# DIFF_DRV.net
KiCad netlist of a schematic drawn in Altium Designer
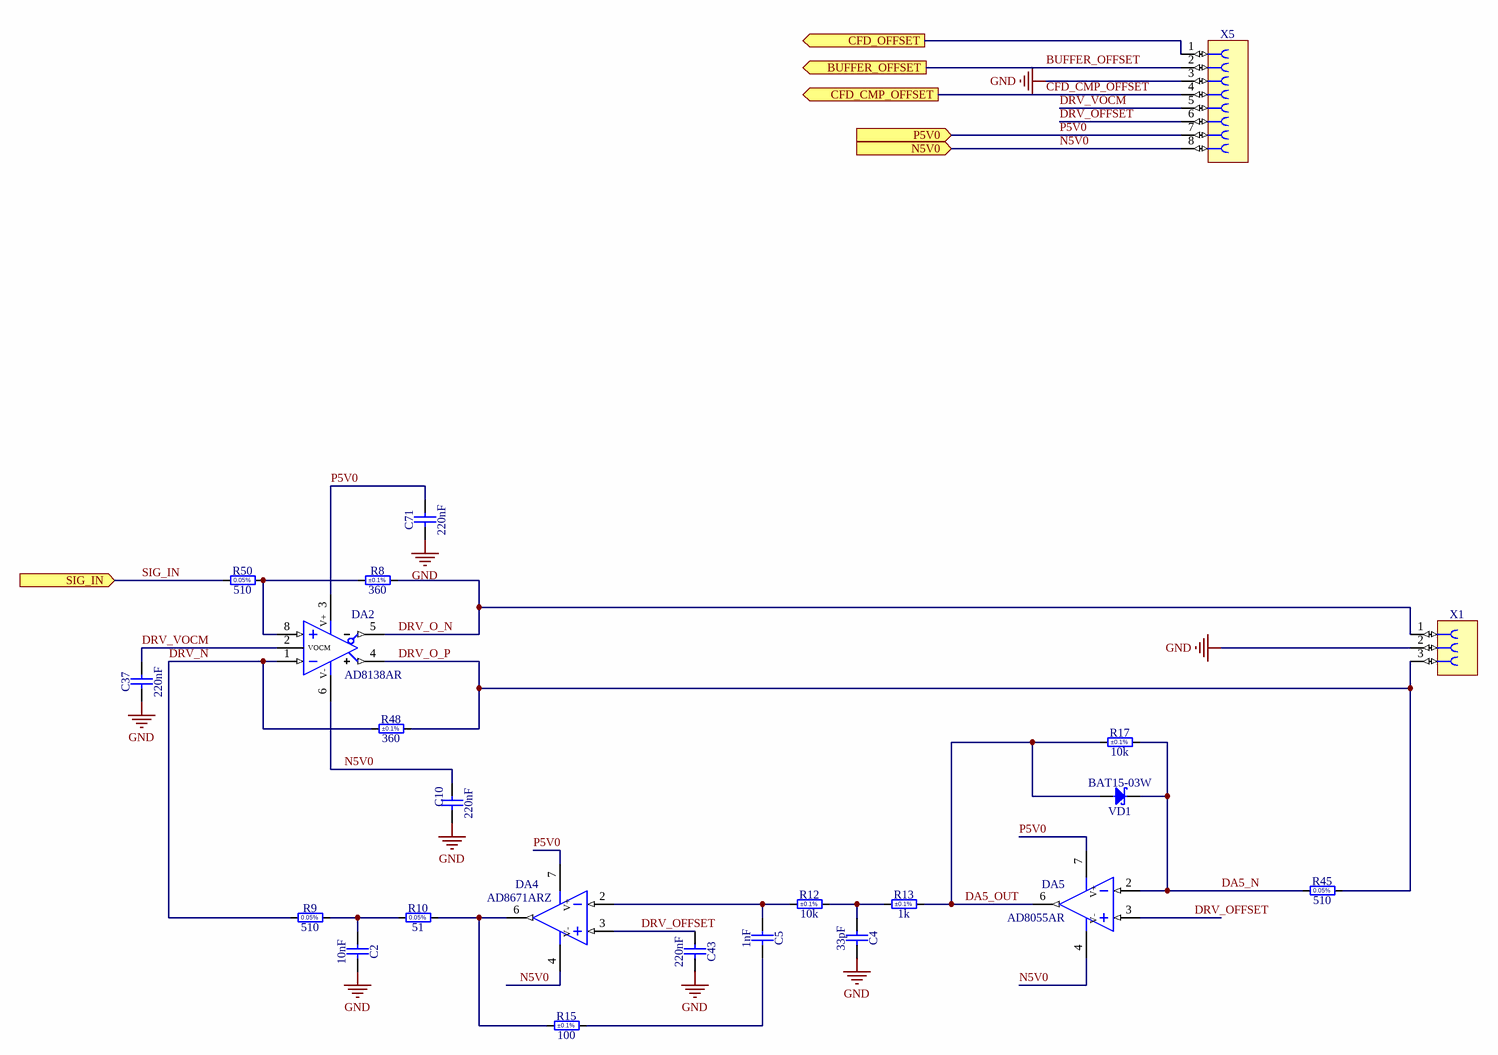
[diagram p0: DIFF_DRV.SchDoc]

(export (version "E")
  (design (tool "Eeschema 10.0.6"))
  (components
    (comp (ref "C2")
      (value "10nF")
      (footprint "CAPC2012X135N")
      (description "Non-polarised capacitor")
      (fields
        (field (name "PART NUMBER") "CC0805_10NF_50V_2%_C0G")
        (field (name "VOLTAGE") "50V")
        (field (name "AUTHOR") "CERN DEM HF")
      )
      (libsource (lib "Capacitors") (part "Capacitor - non polarized"))
    )
    (comp (ref "C4")
      (value "33pF")
      (footprint "CAPC2013X115N")
      (description "Non-polarised capacitor")
      (fields
        (field (name "PART NUMBER") "CC0805_33PF_200V_1%_NP0")
        (field (name "VOLTAGE") "200V")
        (field (name "AUTHOR") "CERN DEM HF")
      )
      (libsource (lib "Capacitors") (part "Capacitor - non polarized"))
    )
    (comp (ref "C5")
      (value "1nF")
      (footprint "CAPC2013X100N")
      (description "Non-polarised capacitor")
      (fields
        (field (name "PART NUMBER") "CC0805_1NF_25V_1%_C0G")
        (field (name "VOLTAGE") "25V")
        (field (name "AUTHOR") "CERN DEM JLC")
      )
      (libsource (lib "Capacitors") (part "Capacitor - non polarized"))
    )
    (comp (ref "C10")
      (value "220nF")
      (footprint "CAPC2012X135N")
      (description "Non-polarised capacitor")
      (fields
        (field (name "PART NUMBER") "CC0805_220NF_50V_10%_X7R")
        (field (name "VOLTAGE") "50V")
        (field (name "AUTHOR") "CERN DEM JLC")
      )
      (libsource (lib "Capacitors") (part "Capacitor - non polarized"))
    )
    (comp (ref "C37")
      (value "220nF")
      (footprint "CAPC2012X135N")
      (description "Non-polarised capacitor")
      (fields
        (field (name "PART NUMBER") "CC0805_220NF_50V_10%_X7R")
        (field (name "VOLTAGE") "50V")
        (field (name "AUTHOR") "CERN DEM JLC")
      )
      (libsource (lib "Capacitors") (part "Capacitor - non polarized"))
    )
    (comp (ref "C43")
      (value "220nF")
      (footprint "CAPC2012X135N")
      (description "Non-polarised capacitor")
      (fields
        (field (name "PART NUMBER") "CC0805_220NF_50V_10%_X7R")
        (field (name "VOLTAGE") "50V")
        (field (name "AUTHOR") "CERN DEM JLC")
      )
      (libsource (lib "Capacitors") (part "Capacitor - non polarized"))
    )
    (comp (ref "C71")
      (value "220nF")
      (footprint "CAPC2012X135N")
      (description "Non-polarised capacitor")
      (fields
        (field (name "PART NUMBER") "CC0805_220NF_50V_10%_X7R")
        (field (name "VOLTAGE") "50V")
        (field (name "AUTHOR") "CERN DEM JLC")
      )
      (libsource (lib "Capacitors") (part "Capacitor - non polarized"))
    )
    (comp (ref "DA2")
      (value "AD8138AR")
      (footprint "SOIC127P600X175-8N")
      (description "Differential Amplifier")
      (fields (field (name "MANUFACTURER") "ANALOG DEVICES") (field (name "AUTHOR") "CERN DEM JLC"))
      (libsource (lib "ICs And Semiconductors") (part "Differential Amplifier Type1"))
    )
    (comp (ref "DA4")
      (value "AD8671ARZ")
      (footprint "SOIC127P600X175-8N")
      (description "Operational Amplifier")
      (fields
        (field (name "MANUFACTURER") "ANALOG DEVICES")
        (field (name "MANUFACTURER PART NUMBER") "AD8671AR")
        (field (name "AUTHOR") "CERN DEM JLC")
      )
      (libsource (lib "ICs And Semiconductors") (part "Operational Amplifier Type1"))
    )
    (comp (ref "DA5")
      (value "AD8055AR")
      (footprint "SOIC127P600X175-8N")
      (description "Operational Amplifier")
      (fields (field (name "MANUFACTURER") "ANALOG DEVICES") (field (name "AUTHOR") "CERN DEM HF"))
      (libsource (lib "ICs And Semiconductors") (part "Operational Amplifier Type1"))
    )
    (comp (ref "R8")
      (value "360")
      (footprint "RESC2012X60N")
      (description "Resistor - 0.1%")
      (fields
        (field (name "TOLERANCE") "±0.1%")
        (field (name "PART NUMBER") "R0805_360R_0.1%_0.125W_10PPM")
        (field (name "POWER") "0.125W")
        (field (name "AUTHOR") "CERN DEM HF")
      )
      (libsource (lib "Resistors") (part "Resistor - 0.1%"))
    )
    (comp (ref "R9")
      (value "510")
      (footprint "RESC1608X55N")
      (description "Resistor - 0.05%")
      (fields
        (field (name "PART NUMBER") "R0603_510R_0.1%_0.1W_10PPM")
        (field (name "POWER") "0.1W")
        (field (name "AUTHOR") "CERN DEM HF")
      )
      (libsource (lib "Resistors") (part "Resistor - 0.05%"))
    )
    (comp (ref "R10")
      (value "51")
      (footprint "RESC2012X60N")
      (description "Resistor - 0.05%")
      (fields
        (field (name "PART NUMBER") "R0805_51R_0.05%_0.125W_10PPM")
        (field (name "POWER") "0.1W")
        (field (name "AUTHOR") "CERN DEM HF")
      )
      (libsource (lib "Resistors") (part "Resistor - 0.05%"))
    )
    (comp (ref "R12")
      (value "10k")
      (footprint "RESC2012X60N")
      (description "Resistor - 0.1%")
      (fields
        (field (name "TOLERANCE") "±0.1%")
        (field (name "PART NUMBER") "R0805_10K_0.1%_0.1W_10PPM")
        (field (name "POWER") "0.1W")
        (field (name "AUTHOR") "CERN DEM JLC")
      )
      (libsource (lib "Resistors") (part "Resistor - 0.1%"))
    )
    (comp (ref "R13")
      (value "1k")
      (footprint "RESC2012X60N")
      (description "Resistor - 0.1%")
      (fields
        (field (name "TOLERANCE") "±0.1%")
        (field (name "PART NUMBER") "R0805_1K_0.1%_0.1W_10PPM")
        (field (name "POWER") "0.1W")
        (field (name "AUTHOR") "CERN DEM JLC")
      )
      (libsource (lib "Resistors") (part "Resistor - 0.1%"))
    )
    (comp (ref "R15")
      (value "100")
      (footprint "RESC2012X60N")
      (description "Resistor - 0.1%")
      (fields
        (field (name "TOLERANCE") "±0.1%")
        (field (name "PART NUMBER") "R0805_100R_0.1%_0.1W_10PPM")
        (field (name "POWER") "0.1W")
        (field (name "AUTHOR") "CERN DEM JLC")
      )
      (libsource (lib "Resistors") (part "Resistor - 0.1%"))
    )
    (comp (ref "R17")
      (value "10k")
      (footprint "RESC2012X60N")
      (description "Resistor - 0.1%")
      (fields
        (field (name "TOLERANCE") "±0.1%")
        (field (name "PART NUMBER") "R0805_10K_0.1%_0.1W_10PPM")
        (field (name "POWER") "0.1W")
        (field (name "AUTHOR") "CERN DEM JLC")
      )
      (libsource (lib "Resistors") (part "Resistor - 0.1%"))
    )
    (comp (ref "R45")
      (value "510")
      (footprint "RESC1608X55N")
      (description "Resistor - 0.05%")
      (fields
        (field (name "PART NUMBER") "R0603_510R_0.1%_0.1W_10PPM")
        (field (name "POWER") "0.1W")
        (field (name "AUTHOR") "CERN DEM HF")
      )
      (libsource (lib "Resistors") (part "Resistor - 0.05%"))
    )
    (comp (ref "R48")
      (value "360")
      (footprint "RESC2012X60N")
      (description "Resistor - 0.1%")
      (fields
        (field (name "TOLERANCE") "±0.1%")
        (field (name "PART NUMBER") "R0805_360R_0.1%_0.125W_10PPM")
        (field (name "POWER") "0.125W")
        (field (name "AUTHOR") "CERN DEM HF")
      )
      (libsource (lib "Resistors") (part "Resistor - 0.1%"))
    )
    (comp (ref "R50")
      (value "510")
      (footprint "RESC1608X55N")
      (description "Resistor - 0.05%")
      (fields
        (field (name "PART NUMBER") "R0603_510R_0.1%_0.1W_10PPM")
        (field (name "POWER") "0.1W")
        (field (name "AUTHOR") "CERN DEM HF")
      )
      (libsource (lib "Resistors") (part "Resistor - 0.05%"))
    )
    (comp (ref "VD1")
      (value "BAT15-03W")
      (footprint "SOD2512X110N")
      (description "Schottky Diode")
      (fields
        (field (name "VOLTAGE") "4V")
        (field (name "POWER") "100mA")
        (field (name "AUTHOR") "CERN DEM HF")
      )
      (libsource (lib "ICs And Semiconductors") (part "Diode Schottky"))
    )
    (comp (ref "X1")
      (value "Socket 3")
      (footprint "SAMTEC_CES-103-01-T-S")
      (description "Connector 3 Female")
      (fields
        (field (name "PART NUMBER") "SAMTEC_CES-103-01-L-S")
        (field (name "MANUFACTURER") "SAMTEC")
        (field (name "AUTHOR") "CERN DEM HF")
      )
      (libsource (lib "Connectors") (part "Connector 3 Female"))
    )
    (comp (ref "X5")
      (value "Socket 8")
      (footprint "SAMTEC_CES-108-01-T-S")
      (description "Connector 8 Female")
      (fields
        (field (name "PART NUMBER") "SAMTEC_CES-108-01-L-S")
        (field (name "MANUFACTURER") "SAMTEC")
        (field (name "AUTHOR") "CERN DEM HF")
      )
      (libsource (lib "Connectors") (part "Connector 8 Female"))
    )
  )
  (nets
    (net (code "1") (name "/BUFFER_OFFSET") (class "Default")
      (node (ref "X5") (pin "2") (pinfunction "2_2") (pintype "bidirectional"))
    )
    (net (code "2") (name "/CFD_CMP_OFFSET") (class "Default")
      (node (ref "X5") (pin "4") (pinfunction "4_4") (pintype "bidirectional"))
    )
    (net (code "3") (name "/CFD_OFFSET") (class "Default")
      (node (ref "X5") (pin "1") (pinfunction "1_1") (pintype "bidirectional"))
    )
    (net (code "4") (name "/DA5_N") (class "Default")
      (node (ref "DA5") (pin "2") (pinfunction "IN-_2") (pintype "input"))
      (node (ref "R17") (pin "1") (pinfunction "1_1") (pintype "passive"))
      (node (ref "R45") (pin "1") (pinfunction "1_1") (pintype "passive"))
      (node (ref "VD1") (pin "1") (pinfunction "C_1") (pintype "passive"))
    )
    (net (code "5") (name "/DA5_OUT") (class "Default")
      (node (ref "DA5") (pin "6") (pinfunction "OUT_6") (pintype "output"))
      (node (ref "R13") (pin "1") (pinfunction "1_1") (pintype "passive"))
      (node (ref "R17") (pin "2") (pinfunction "2_2") (pintype "passive"))
      (node (ref "VD1") (pin "2") (pinfunction "A_2") (pintype "passive"))
    )
    (net (code "6") (name "/DRV_N") (class "Default")
      (node (ref "DA2") (pin "1") (pinfunction "IN-_1") (pintype "input"))
      (node (ref "R48") (pin "1") (pinfunction "1_1") (pintype "passive"))
      (node (ref "R9") (pin "2") (pinfunction "2_2") (pintype "passive"))
    )
    (net (code "7") (name "/DRV_OFFSET") (class "Default")
      (node (ref "C43") (pin "2") (pinfunction "2_2") (pintype "passive"))
      (node (ref "DA4") (pin "3") (pinfunction "IN+_3") (pintype "input"))
      (node (ref "DA5") (pin "3") (pinfunction "IN+_3") (pintype "input"))
      (node (ref "X5") (pin "6") (pinfunction "6_6") (pintype "bidirectional"))
    )
    (net (code "8") (name "/DRV_O_N") (class "Default")
      (node (ref "DA2") (pin "5") (pinfunction "VOUT-_5") (pintype "output"))
      (node (ref "R8") (pin "2") (pinfunction "2_2") (pintype "passive"))
      (node (ref "X1") (pin "1") (pinfunction "1_1") (pintype "bidirectional"))
    )
    (net (code "9") (name "/DRV_O_P") (class "Default")
      (node (ref "DA2") (pin "4") (pinfunction "VOUT+_4") (pintype "output"))
      (node (ref "R45") (pin "2") (pinfunction "2_2") (pintype "passive"))
      (node (ref "R48") (pin "2") (pinfunction "2_2") (pintype "passive"))
      (node (ref "X1") (pin "3") (pinfunction "3_3") (pintype "bidirectional"))
    )
    (net (code "10") (name "/DRV_VOCM") (class "Default")
      (node (ref "C37") (pin "2") (pinfunction "2_2") (pintype "passive"))
      (node (ref "DA2") (pin "2") (pinfunction "VOCM_2") (pintype "passive"))
      (node (ref "X5") (pin "5") (pinfunction "5_5") (pintype "bidirectional"))
    )
    (net (code "11") (name "/N5V0") (class "Default")
      (node (ref "C10") (pin "2") (pinfunction "2_2") (pintype "passive"))
      (node (ref "DA2") (pin "6") (pinfunction "V-_6") (pintype "power_in"))
      (node (ref "DA4") (pin "4") (pinfunction "V-_4") (pintype "power_in"))
      (node (ref "DA5") (pin "4") (pinfunction "V-_4") (pintype "power_in"))
      (node (ref "X5") (pin "8") (pinfunction "8_8") (pintype "bidirectional"))
    )
    (net (code "12") (name "/P5V0") (class "Default")
      (node (ref "C71") (pin "2") (pinfunction "2_2") (pintype "passive"))
      (node (ref "DA2") (pin "3") (pinfunction "V+_3") (pintype "power_in"))
      (node (ref "DA4") (pin "7") (pinfunction "V+_7") (pintype "power_in"))
      (node (ref "DA5") (pin "7") (pinfunction "V+_7") (pintype "power_in"))
      (node (ref "X5") (pin "7") (pinfunction "7_7") (pintype "bidirectional"))
    )
    (net (code "13") (name "/SIG_IN") (class "Default")
      (node (ref "R50") (pin "1") (pinfunction "1_1") (pintype "passive"))
    )
    (net (code "14") (name "GND") (class "Default")
      (node (ref "C10") (pin "1") (pinfunction "1_1") (pintype "passive"))
      (node (ref "C2") (pin "1") (pinfunction "1_1") (pintype "passive"))
      (node (ref "C37") (pin "1") (pinfunction "1_1") (pintype "passive"))
      (node (ref "C4") (pin "1") (pinfunction "1_1") (pintype "passive"))
      (node (ref "C43") (pin "1") (pinfunction "1_1") (pintype "passive"))
      (node (ref "C71") (pin "1") (pinfunction "1_1") (pintype "passive"))
      (node (ref "X1") (pin "2") (pinfunction "2_2") (pintype "bidirectional"))
      (node (ref "X5") (pin "3") (pinfunction "3_3") (pintype "bidirectional"))
    )
    (net (code "15") (name "Net-(C2-Pad2)") (class "Default")
      (node (ref "C2") (pin "2") (pinfunction "2_2") (pintype "passive"))
      (node (ref "R10") (pin "2") (pinfunction "2_2") (pintype "passive"))
      (node (ref "R9") (pin "1") (pinfunction "1_1") (pintype "passive"))
    )
    (net (code "16") (name "Net-(C4-Pad2)") (class "Default")
      (node (ref "C4") (pin "2") (pinfunction "2_2") (pintype "passive"))
      (node (ref "R12") (pin "1") (pinfunction "1_1") (pintype "passive"))
      (node (ref "R13") (pin "2") (pinfunction "2_2") (pintype "passive"))
    )
    (net (code "17") (name "Net-(C5-Pad1)") (class "Default")
      (node (ref "C5") (pin "1") (pinfunction "1_1") (pintype "passive"))
      (node (ref "R15") (pin "1") (pinfunction "1_1") (pintype "passive"))
    )
    (net (code "18") (name "Net-(DA2-IN+)") (class "Default")
      (node (ref "DA2") (pin "8") (pinfunction "IN+_8") (pintype "input"))
      (node (ref "R50") (pin "2") (pinfunction "2_2") (pintype "passive"))
      (node (ref "R8") (pin "1") (pinfunction "1_1") (pintype "passive"))
    )
    (net (code "19") (name "Net-(DA4-IN-)") (class "Default")
      (node (ref "C5") (pin "2") (pinfunction "2_2") (pintype "passive"))
      (node (ref "DA4") (pin "2") (pinfunction "IN-_2") (pintype "input"))
      (node (ref "R12") (pin "2") (pinfunction "2_2") (pintype "passive"))
    )
    (net (code "20") (name "Net-(DA4-OUT)") (class "Default")
      (node (ref "DA4") (pin "6") (pinfunction "OUT_6") (pintype "output"))
      (node (ref "R10") (pin "1") (pinfunction "1_1") (pintype "passive"))
      (node (ref "R15") (pin "2") (pinfunction "2_2") (pintype "passive"))
    )
  )
)
